# door_clock_ver2.net
KiCad netlist of a schematic drawn in Altium Designer
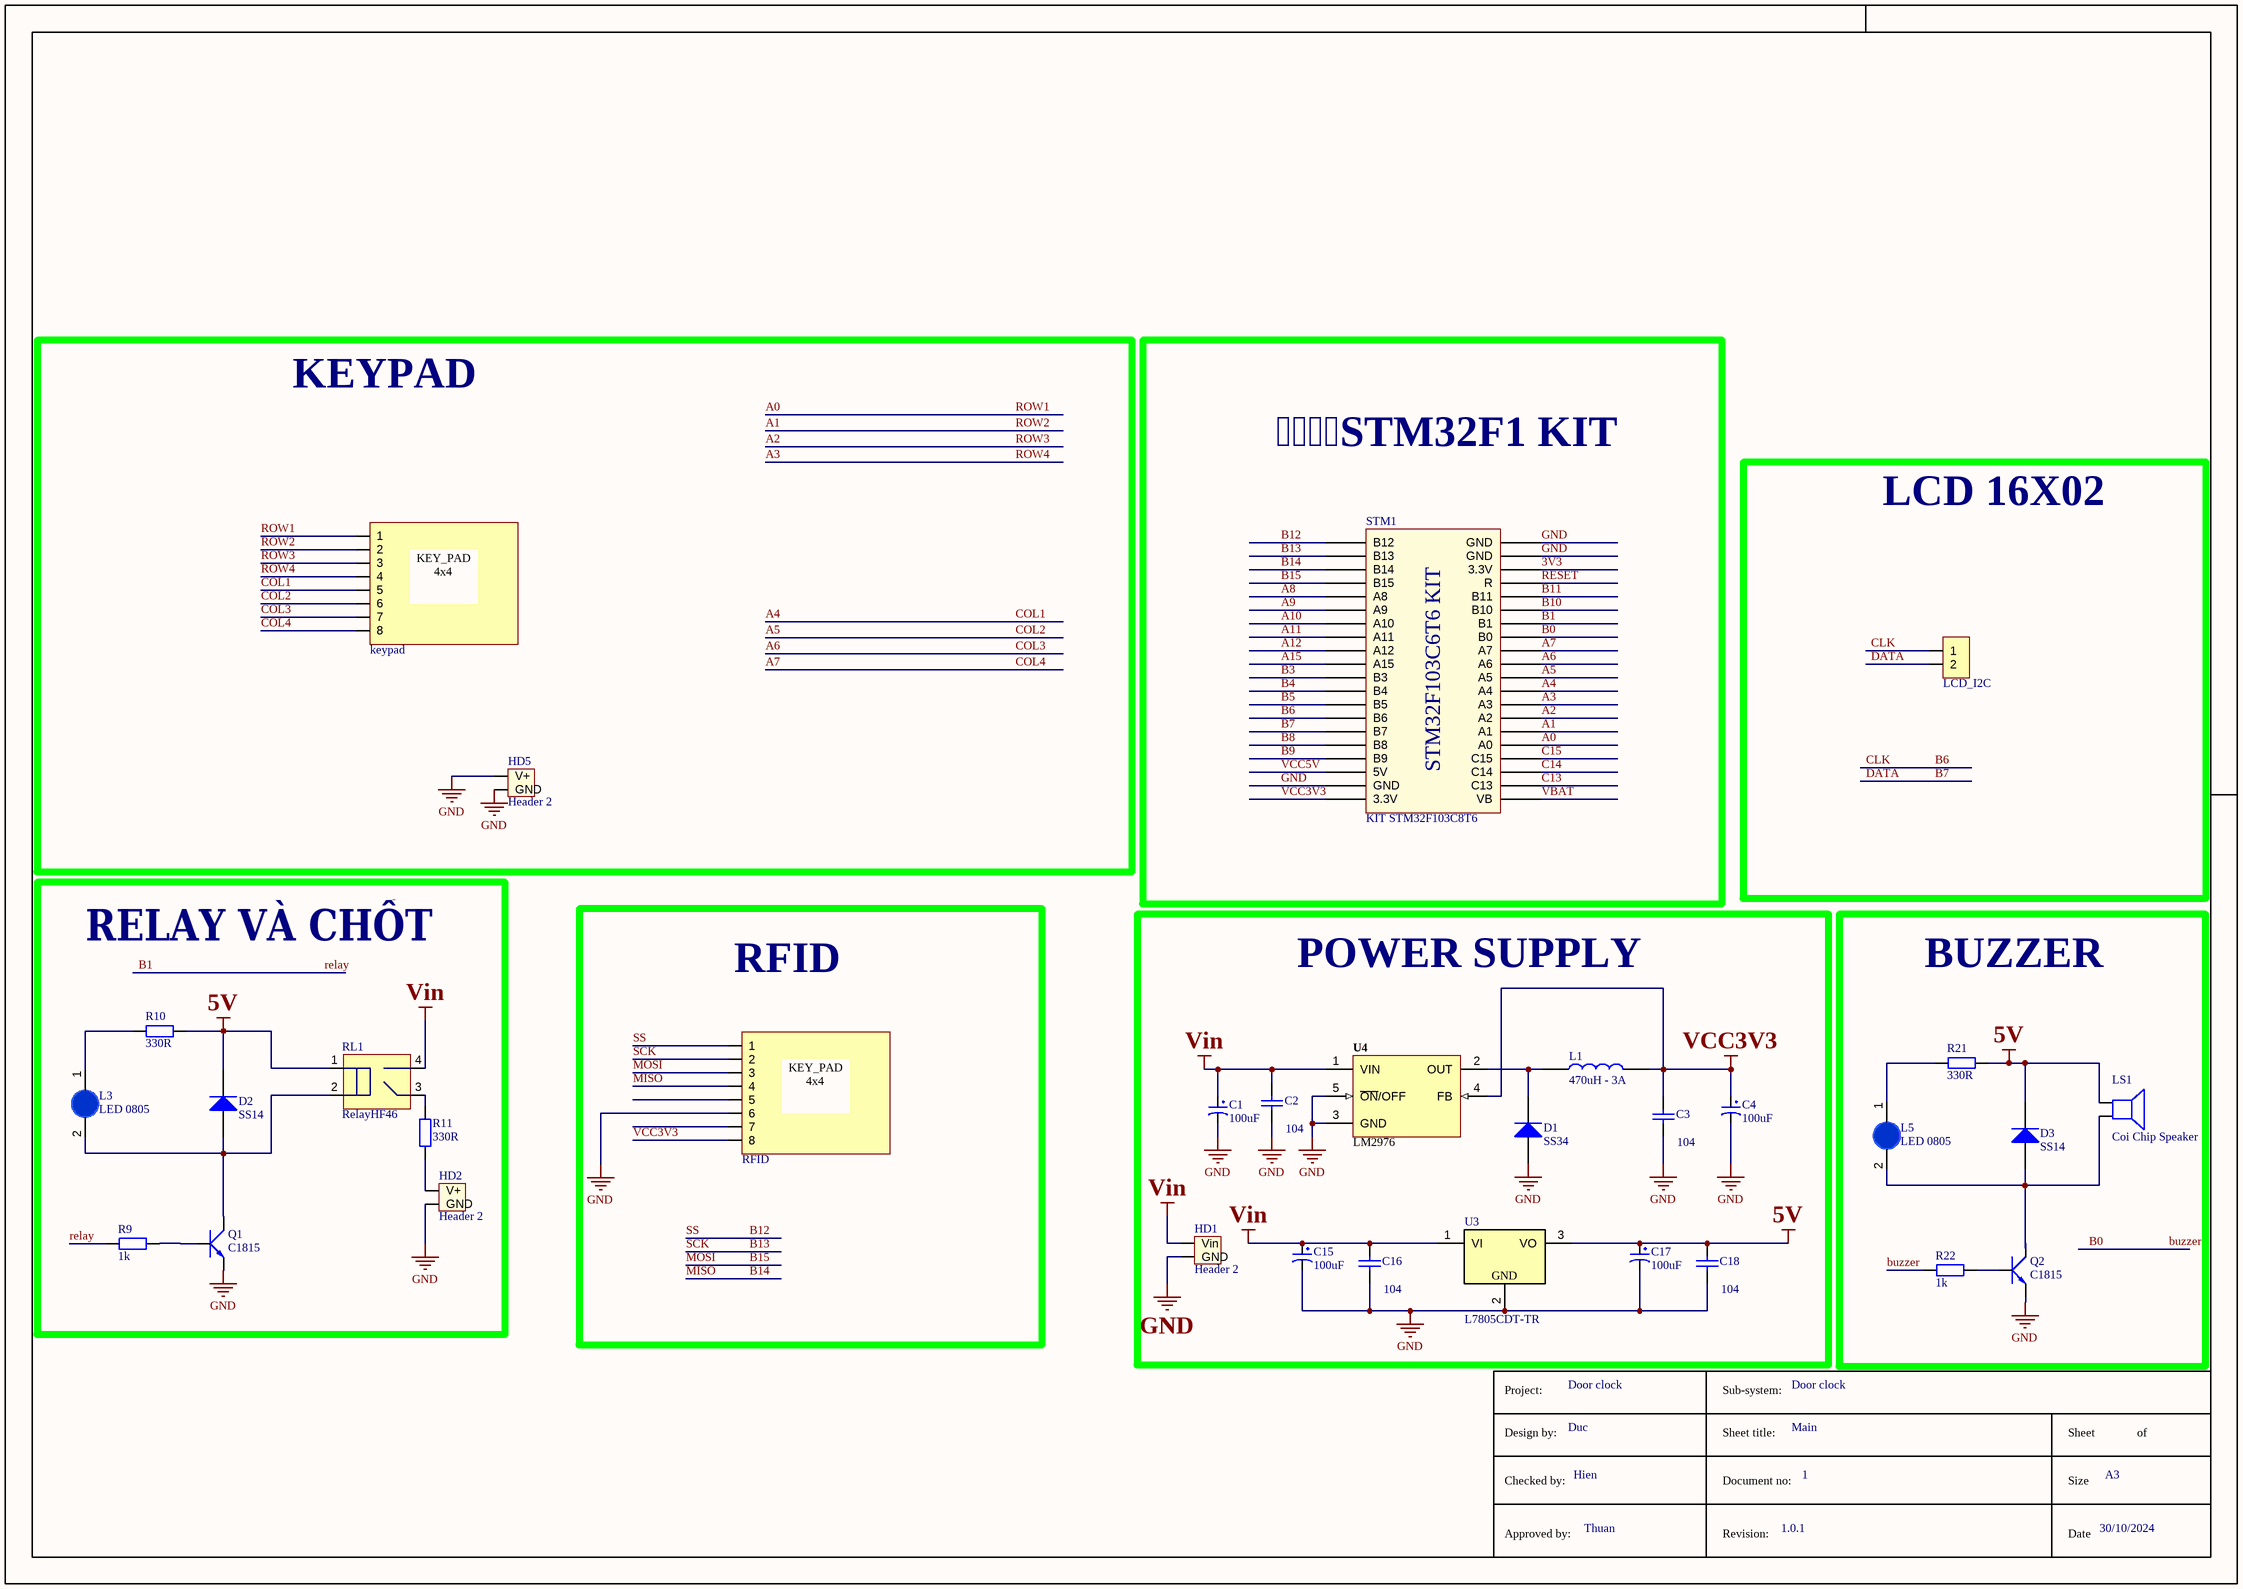
[diagram p0: door_clock_ver2.SchDoc]

(export (version "E")
  (design (tool "Eeschema 10.0.6"))
  (components
    (comp (ref "C1")
      (value "100uF")
      (footprint "tu hoa 8mm")
      (description "Cắm")
      (libsource (lib "Altium_Lib_by_KhueNguyenCreator") (part "Tu Hoa 100uF 50V 8x11"))
    )
    (comp (ref "C2")
      (value "104")
      (footprint "tu 0805")
      (description "Dán")
      (libsource (lib "Altium_Lib_by_KhueNguyenCreator") (part "Tu 0805 104 50V 10%"))
    )
    (comp (ref "C3")
      (value "104")
      (footprint "tu 0805")
      (description "Dán")
      (libsource (lib "Altium_Lib_by_KhueNguyenCreator") (part "Tu 0805 104 50V 10%"))
    )
    (comp (ref "C4")
      (value "100uF")
      (footprint "tu hoa 8mm")
      (description "Cắm")
      (libsource (lib "Altium_Lib_by_KhueNguyenCreator") (part "Tu Hoa 100uF 50V 8x11"))
    )
    (comp (ref "C15")
      (value "100uF")
      (footprint "tu hoa 8mm")
      (description "Cắm")
      (libsource (lib "Altium_Lib_by_KhueNguyenCreator") (part "Tu Hoa 100uF 50V 8x11"))
    )
    (comp (ref "C16")
      (value "104")
      (footprint "tu 0805")
      (description "Dán")
      (libsource (lib "Altium_Lib_by_KhueNguyenCreator") (part "Tu 0805 104 50V 10%"))
    )
    (comp (ref "C17")
      (value "100uF")
      (footprint "tu hoa 8mm")
      (description "Cắm")
      (libsource (lib "Altium_Lib_by_KhueNguyenCreator") (part "Tu Hoa 100uF 50V 8x11"))
    )
    (comp (ref "C18")
      (value "104")
      (footprint "tu 0805")
      (description "Dán")
      (libsource (lib "Altium_Lib_by_KhueNguyenCreator") (part "Tu 0805 104 50V 10%"))
    )
    (comp (ref "D1")
      (value "SS34")
      (footprint "DIODE SMA")
      (description "Dán")
      (libsource (lib "Altium_Lib_by_KhueNguyenCreator") (part "Diode SS34 ( 1N5822 )"))
    )
    (comp (ref "D2")
      (value "SS14")
      (footprint "DIODE SMA")
      (description "Dán")
      (libsource (lib "Altium_Lib_by_KhueNguyenCreator") (part "Diode SS14 ( 1N5819)"))
    )
    (comp (ref "D3")
      (value "SS14")
      (footprint "DIODE SMA")
      (description "Dán")
      (libsource (lib "Altium_Lib_by_KhueNguyenCreator") (part "Diode SS14 ( 1N5819)"))
    )
    (comp (ref "HD1")
      (value "Header 2")
      (footprint "HED2")
      (description "Header 2 (Green)")
      (libsource (lib "syhaunguyen") (part "Hed2"))
    )
    (comp (ref "HD2")
      (value "Header 2")
      (footprint "HED2")
      (description "Header 2 (Green)")
      (libsource (lib "syhaunguyen") (part "Hed2"))
    )
    (comp (ref "HD5")
      (value "Header 2")
      (footprint "HED2")
      (description "Header 2 (Green)")
      (libsource (lib "syhaunguyen") (part "Hed2"))
    )
    (comp (ref "JP25")
      (value "keypad")
      (footprint "JP 1x8 DT")
      (description "Cắm")
      (libsource (lib "Altium_Lib_by_KhueNguyenCreator") (part "JP 1x8 2.54 Duc Thang"))
    )
    (comp (ref "JP26")
      (value "RFID")
      (footprint "JP 1x8 DT")
      (description "Cắm")
      (libsource (lib "Altium_Lib_by_KhueNguyenCreator") (part "JP 1x8 2.54 Duc Thang"))
    )
    (comp (ref "JP27")
      (value "LCD_I2C")
      (footprint "JP 1x2 DT")
      (description "Cắm")
      (libsource (lib "Altium_Lib_by_KhueNguyenCreator") (part "JP 1x2 2.54 Duc Thang"))
    )
    (comp (ref "L1")
      (value "470uH - 3A")
      (footprint "CUON CAM 100uH3A")
      (description "Cắm")
      (libsource (lib "Altium_Lib_by_KhueNguyenCreator") (part "CUON CAM 470uH DIP"))
    )
    (comp (ref "L3")
      (value "LED 0805")
      (footprint "LED-0805-Blue")
      (description "Dán")
      (libsource (lib "Altium_Lib_by_KhueNguyenCreator") (part "LED 0805 Xanh Duong"))
    )
    (comp (ref "L5")
      (value "LED 0805")
      (footprint "LED-0805-Blue")
      (description "Dán")
      (libsource (lib "Altium_Lib_by_KhueNguyenCreator") (part "LED 0805 Xanh Duong"))
    )
    (comp (ref "LS1")
      (value "Coi Chip Speaker")
      (footprint "Coi Chip Speacker")
      (description "Còi chip")
      (libsource (lib "Altium_Lib_by_KhueNguyenCreator") (part "Coi Chip Speaker"))
    )
    (comp (ref "Q1")
      (value "C1815")
      (footprint "TO92")
      (description "NPN transistor")
      (libsource (lib "Altium_Lib_by_KhueNguyenCreator") (part "Trans C1815 DIP"))
    )
    (comp (ref "Q2")
      (value "C1815")
      (footprint "TO92")
      (description "NPN transistor")
      (libsource (lib "Altium_Lib_by_KhueNguyenCreator") (part "Trans C1815 DIP"))
    )
    (comp (ref "R9")
      (value "1k")
      (footprint "tro smd 0805")
      (description "Dán")
      (libsource (lib "Altium_Lib_by_KhueNguyenCreator") (part "Tro 0805 1% 1k"))
    )
    (comp (ref "R10")
      (value "330R")
      (footprint "Tro SMD 0805")
      (description "Dán")
      (libsource (lib "Altium_Lib_by_KhueNguyenCreator") (part "Tro 0805 5% 330R"))
    )
    (comp (ref "R11")
      (value "330R")
      (footprint "Tro SMD 0805")
      (description "Dán")
      (libsource (lib "Altium_Lib_by_KhueNguyenCreator") (part "Tro 0805 5% 330R"))
    )
    (comp (ref "R21")
      (value "330R")
      (footprint "Tro SMD 0805")
      (description "Dán")
      (libsource (lib "Altium_Lib_by_KhueNguyenCreator") (part "Tro 0805 5% 330R"))
    )
    (comp (ref "R22")
      (value "1k")
      (footprint "tro smd 0805")
      (description "Dán")
      (libsource (lib "Altium_Lib_by_KhueNguyenCreator") (part "Tro 0805 1% 1k"))
    )
    (comp (ref "RL1")
      (value "RelayHF46")
      (footprint "Relay 4 chan HF46F")
      (description "Relay 4 chan HF46F")
      (libsource (lib "Altium_Lib_by_KhueNguyenCreator") (part "Relay 4 chan HF46F"))
    )
    (comp (ref "STM1")
      (value "KIT STM32F103C8T6")
      (footprint "STM32F103 KIT")
      (description "KIT STM32F103C8T6 Bluepill")
      (libsource (lib "Altium_Lib_by_KhueNguyenCreator") (part "STM32f103 Bluepill"))
    )
    (comp (ref "U3")
      (value "L7805CDT-TR")
      (footprint "DPAK_118_446_112X59_SMD")
      (description "Linear Voltage Regulator IC 1 Output 1.5A DPAK")
      (fields (field (name "MANUFACTURER") "Diodes"))
      (libsource (lib "Altium_Lib_by_KhueNguyenCreator") (part "REG_35V_5V-1.5A-7.5W-DPAK"))
    )
    (comp (ref "U4")
      (value "LM2976")
      (footprint "TO263")
      (libsource (lib "KhanhBK_SCH_Library_1") (part "LM2596"))
    )
  )
  (nets
    (net (code "1") (name "/3V3") (class "Default")
      (node (ref "STM1") (pin "38") (pinfunction "3.3V_38") (pintype "passive"))
    )
    (net (code "2") (name "/A0") (class "Default")
      (node (ref "JP25") (pin "1") (pinfunction "1_1") (pintype "passive"))
      (node (ref "STM1") (pin "25") (pinfunction "A0_25") (pintype "passive"))
    )
    (net (code "3") (name "/A1") (class "Default")
      (node (ref "JP25") (pin "2") (pinfunction "2_2") (pintype "passive"))
      (node (ref "STM1") (pin "26") (pinfunction "A1_26") (pintype "passive"))
    )
    (net (code "4") (name "/A2") (class "Default")
      (node (ref "JP25") (pin "3") (pinfunction "3_3") (pintype "passive"))
      (node (ref "STM1") (pin "27") (pinfunction "A2_27") (pintype "passive"))
    )
    (net (code "5") (name "/A3") (class "Default")
      (node (ref "JP25") (pin "4") (pinfunction "4_4") (pintype "passive"))
      (node (ref "STM1") (pin "28") (pinfunction "A3_28") (pintype "passive"))
    )
    (net (code "6") (name "/A4") (class "Default")
      (node (ref "JP25") (pin "5") (pinfunction "5_5") (pintype "passive"))
      (node (ref "STM1") (pin "29") (pinfunction "A4_29") (pintype "passive"))
    )
    (net (code "7") (name "/A5") (class "Default")
      (node (ref "JP25") (pin "6") (pinfunction "6_6") (pintype "passive"))
      (node (ref "STM1") (pin "30") (pinfunction "A5_30") (pintype "passive"))
    )
    (net (code "8") (name "/A6") (class "Default")
      (node (ref "JP25") (pin "7") (pinfunction "7_7") (pintype "passive"))
      (node (ref "STM1") (pin "31") (pinfunction "A6_31") (pintype "passive"))
    )
    (net (code "9") (name "/A7") (class "Default")
      (node (ref "JP25") (pin "8") (pinfunction "8_8") (pintype "passive"))
      (node (ref "STM1") (pin "32") (pinfunction "A7_32") (pintype "passive"))
    )
    (net (code "10") (name "/A8") (class "Default")
      (node (ref "STM1") (pin "5") (pinfunction "A8_5") (pintype "passive"))
    )
    (net (code "11") (name "/A9") (class "Default")
      (node (ref "STM1") (pin "6") (pinfunction "A9_6") (pintype "passive"))
    )
    (net (code "12") (name "/A10") (class "Default")
      (node (ref "STM1") (pin "7") (pinfunction "A10_7") (pintype "passive"))
    )
    (net (code "13") (name "/A11") (class "Default")
      (node (ref "STM1") (pin "8") (pinfunction "A11_8") (pintype "passive"))
    )
    (net (code "14") (name "/A12") (class "Default")
      (node (ref "STM1") (pin "9") (pinfunction "A12_9") (pintype "passive"))
    )
    (net (code "15") (name "/A15") (class "Default")
      (node (ref "STM1") (pin "10") (pinfunction "A15_10") (pintype "passive"))
    )
    (net (code "16") (name "/B0") (class "Default")
      (node (ref "R22") (pin "1") (pinfunction "1_1") (pintype "passive"))
      (node (ref "STM1") (pin "33") (pinfunction "B0_33") (pintype "passive"))
    )
    (net (code "17") (name "/B1") (class "Default")
      (node (ref "R9") (pin "1") (pinfunction "1_1") (pintype "passive"))
      (node (ref "STM1") (pin "34") (pinfunction "B1_34") (pintype "passive"))
    )
    (net (code "18") (name "/B3") (class "Default")
      (node (ref "STM1") (pin "11") (pinfunction "B3_11") (pintype "passive"))
    )
    (net (code "19") (name "/B4") (class "Default")
      (node (ref "STM1") (pin "12") (pinfunction "B4_12") (pintype "passive"))
    )
    (net (code "20") (name "/B5") (class "Default")
      (node (ref "STM1") (pin "13") (pinfunction "B5_13") (pintype "passive"))
    )
    (net (code "21") (name "/B6") (class "Default")
      (node (ref "JP27") (pin "1") (pinfunction "1_1") (pintype "passive"))
      (node (ref "STM1") (pin "14") (pinfunction "B6_14") (pintype "passive"))
    )
    (net (code "22") (name "/B7") (class "Default")
      (node (ref "JP27") (pin "2") (pinfunction "2_2") (pintype "passive"))
      (node (ref "STM1") (pin "15") (pinfunction "B7_15") (pintype "passive"))
    )
    (net (code "23") (name "/B8") (class "Default")
      (node (ref "STM1") (pin "16") (pinfunction "B8_16") (pintype "passive"))
    )
    (net (code "24") (name "/B9") (class "Default")
      (node (ref "STM1") (pin "17") (pinfunction "B9_17") (pintype "passive"))
    )
    (net (code "25") (name "/B10") (class "Default")
      (node (ref "STM1") (pin "35") (pinfunction "B10_35") (pintype "passive"))
    )
    (net (code "26") (name "/B11") (class "Default")
      (node (ref "STM1") (pin "36") (pinfunction "B11_36") (pintype "passive"))
    )
    (net (code "27") (name "/B12") (class "Default")
      (node (ref "JP26") (pin "1") (pinfunction "1_1") (pintype "passive"))
      (node (ref "STM1") (pin "1") (pinfunction "B12_1") (pintype "passive"))
    )
    (net (code "28") (name "/B13") (class "Default")
      (node (ref "JP26") (pin "2") (pinfunction "2_2") (pintype "passive"))
      (node (ref "STM1") (pin "2") (pinfunction "B13_2") (pintype "passive"))
    )
    (net (code "29") (name "/B14") (class "Default")
      (node (ref "JP26") (pin "4") (pinfunction "4_4") (pintype "passive"))
      (node (ref "STM1") (pin "3") (pinfunction "B14_3") (pintype "passive"))
    )
    (net (code "30") (name "/B15") (class "Default")
      (node (ref "JP26") (pin "3") (pinfunction "3_3") (pintype "passive"))
      (node (ref "STM1") (pin "4") (pinfunction "B15_4") (pintype "passive"))
    )
    (net (code "31") (name "/C13") (class "Default")
      (node (ref "STM1") (pin "22") (pinfunction "C13_22") (pintype "passive"))
    )
    (net (code "32") (name "/C14") (class "Default")
      (node (ref "STM1") (pin "23") (pinfunction "C14_23") (pintype "passive"))
    )
    (net (code "33") (name "/C15") (class "Default")
      (node (ref "STM1") (pin "24") (pinfunction "C15_24") (pintype "passive"))
    )
    (net (code "34") (name "/RESET") (class "Default")
      (node (ref "STM1") (pin "37") (pinfunction "R_37") (pintype "passive"))
    )
    (net (code "35") (name "/VBAT") (class "Default")
      (node (ref "STM1") (pin "21") (pinfunction "VB_21") (pintype "passive"))
    )
    (net (code "36") (name "/VCC5V") (class "Default")
      (node (ref "STM1") (pin "18") (pinfunction "5V_18") (pintype "passive"))
    )
    (net (code "37") (name "5V") (class "Default")
      (node (ref "C17") (pin "1") (pinfunction "1_1") (pintype "passive"))
      (node (ref "C18") (pin "1") (pinfunction "1_1") (pintype "passive"))
      (node (ref "D2") (pin "2") (pinfunction "K_2") (pintype "passive"))
      (node (ref "D3") (pin "2") (pinfunction "K_2") (pintype "passive"))
      (node (ref "LS1") (pin "1") (pinfunction "1_1") (pintype "passive"))
      (node (ref "R10") (pin "2") (pinfunction "2_2") (pintype "passive"))
      (node (ref "R21") (pin "2") (pinfunction "2_2") (pintype "passive"))
      (node (ref "RL1") (pin "1") (pintype "passive"))
      (node (ref "U3") (pin "3") (pinfunction "VO_3") (pintype "passive"))
    )
    (net (code "38") (name "GND") (class "Default")
      (node (ref "C1") (pin "2") (pinfunction "2_2") (pintype "passive"))
      (node (ref "C15") (pin "2") (pinfunction "2_2") (pintype "passive"))
      (node (ref "C16") (pin "2") (pinfunction "2_2") (pintype "passive"))
      (node (ref "C17") (pin "2") (pinfunction "2_2") (pintype "passive"))
      (node (ref "C18") (pin "2") (pinfunction "2_2") (pintype "passive"))
      (node (ref "C2") (pin "2") (pinfunction "2_2") (pintype "passive"))
      (node (ref "C3") (pin "2") (pinfunction "2_2") (pintype "passive"))
      (node (ref "C4") (pin "2") (pinfunction "2_2") (pintype "passive"))
      (node (ref "D1") (pin "1") (pinfunction "A_1") (pintype "passive"))
      (node (ref "HD1") (pin "2") (pinfunction "GND_2") (pintype "passive"))
      (node (ref "HD2") (pin "2") (pinfunction "GND_2") (pintype "passive"))
      (node (ref "HD5") (pin "1") (pinfunction "V+_1") (pintype "passive"))
      (node (ref "HD5") (pin "2") (pinfunction "GND_2") (pintype "passive"))
      (node (ref "JP26") (pin "6") (pinfunction "6_6") (pintype "passive"))
      (node (ref "Q1") (pin "1") (pinfunction "E_1") (pintype "passive"))
      (node (ref "Q2") (pin "1") (pinfunction "E_1") (pintype "passive"))
      (node (ref "STM1") (pin "19") (pinfunction "GND_19") (pintype "passive"))
      (node (ref "STM1") (pin "39") (pinfunction "GND_39") (pintype "passive"))
      (node (ref "STM1") (pin "40") (pinfunction "GND_40") (pintype "passive"))
      (node (ref "U3") (pin "2") (pintype "passive"))
      (node (ref "U4") (pin "3") (pinfunction "GND_3") (pintype "power_in"))
      (node (ref "U4") (pin "5") (pinfunction "~{ON}/OFF_5") (pintype "input"))
    )
    (net (code "39") (name "Net-(D1-K)") (class "Default")
      (node (ref "D1") (pin "2") (pinfunction "K_2") (pintype "passive"))
      (node (ref "L1") (pin "1") (pinfunction "1_1") (pintype "passive"))
      (node (ref "U4") (pin "2") (pinfunction "OUT_2") (pintype "power_in"))
    )
    (net (code "40") (name "Net-(D2-A)") (class "Default")
      (node (ref "D2") (pin "1") (pinfunction "A_1") (pintype "passive"))
      (node (ref "L3") (pin "2") (pinfunction "K_2") (pintype "passive"))
      (node (ref "Q1") (pin "2") (pinfunction "C_2") (pintype "passive"))
      (node (ref "RL1") (pin "2") (pintype "passive"))
    )
    (net (code "41") (name "Net-(D3-A)") (class "Default")
      (node (ref "D3") (pin "1") (pinfunction "A_1") (pintype "passive"))
      (node (ref "L5") (pin "2") (pinfunction "K_2") (pintype "passive"))
      (node (ref "LS1") (pin "2") (pinfunction "2_2") (pintype "passive"))
      (node (ref "Q2") (pin "2") (pinfunction "C_2") (pintype "passive"))
    )
    (net (code "42") (name "Net-(HD2-V+)") (class "Default")
      (node (ref "HD2") (pin "1") (pinfunction "V+_1") (pintype "passive"))
      (node (ref "R11") (pin "1") (pinfunction "1_1") (pintype "passive"))
    )
    (net (code "43") (name "Net-(L3-A)") (class "Default")
      (node (ref "L3") (pin "1") (pinfunction "A_1") (pintype "passive"))
      (node (ref "R10") (pin "1") (pinfunction "1_1") (pintype "passive"))
    )
    (net (code "44") (name "Net-(L5-A)") (class "Default")
      (node (ref "L5") (pin "1") (pinfunction "A_1") (pintype "passive"))
      (node (ref "R21") (pin "1") (pinfunction "1_1") (pintype "passive"))
    )
    (net (code "45") (name "Net-(Q1-B)") (class "Default")
      (node (ref "Q1") (pin "3") (pinfunction "B_3") (pintype "passive"))
      (node (ref "R9") (pin "2") (pinfunction "2_2") (pintype "passive"))
    )
    (net (code "46") (name "Net-(Q2-B)") (class "Default")
      (node (ref "Q2") (pin "3") (pinfunction "B_3") (pintype "passive"))
      (node (ref "R22") (pin "2") (pinfunction "2_2") (pintype "passive"))
    )
    (net (code "47") (name "Net-(R11-Pad2)") (class "Default")
      (node (ref "R11") (pin "2") (pinfunction "2_2") (pintype "passive"))
      (node (ref "RL1") (pin "3") (pinfunction "AC/DC_3") (pintype "passive"))
    )
    (net (code "48") (name "VCC3V3") (class "Default")
      (node (ref "C3") (pin "1") (pinfunction "1_1") (pintype "passive"))
      (node (ref "C4") (pin "1") (pinfunction "1_1") (pintype "passive"))
      (node (ref "JP26") (pin "8") (pinfunction "8_8") (pintype "passive"))
      (node (ref "L1") (pin "2") (pinfunction "2_2") (pintype "passive"))
      (node (ref "STM1") (pin "20") (pinfunction "3.3V_20") (pintype "passive"))
      (node (ref "U4") (pin "4") (pinfunction "FB_4") (pintype "input"))
    )
    (net (code "49") (name "Vin") (class "Default")
      (node (ref "C1") (pin "1") (pinfunction "1_1") (pintype "passive"))
      (node (ref "C15") (pin "1") (pinfunction "1_1") (pintype "passive"))
      (node (ref "C16") (pin "1") (pinfunction "1_1") (pintype "passive"))
      (node (ref "C2") (pin "1") (pinfunction "1_1") (pintype "passive"))
      (node (ref "HD1") (pin "1") (pinfunction "V+_1") (pintype "passive"))
      (node (ref "RL1") (pin "4") (pinfunction "AC/DC_4") (pintype "passive"))
      (node (ref "U3") (pin "1") (pinfunction "VI_1") (pintype "passive"))
      (node (ref "U4") (pin "1") (pinfunction "VIN_1") (pintype "power_in"))
    )
    (net (code "50") (name "unconnected-(JP26-Pad5)") (class "Default")
      (node (ref "JP26") (pin "5") (pinfunction "5_5") (pintype "passive"))
    )
    (net (code "51") (name "unconnected-(JP26-Pad7)") (class "Default")
      (node (ref "JP26") (pin "7") (pinfunction "7_7") (pintype "passive"))
    )
  )
)
